# driver_V1_3.net
KiCad netlist of a schematic drawn in Altium Designer
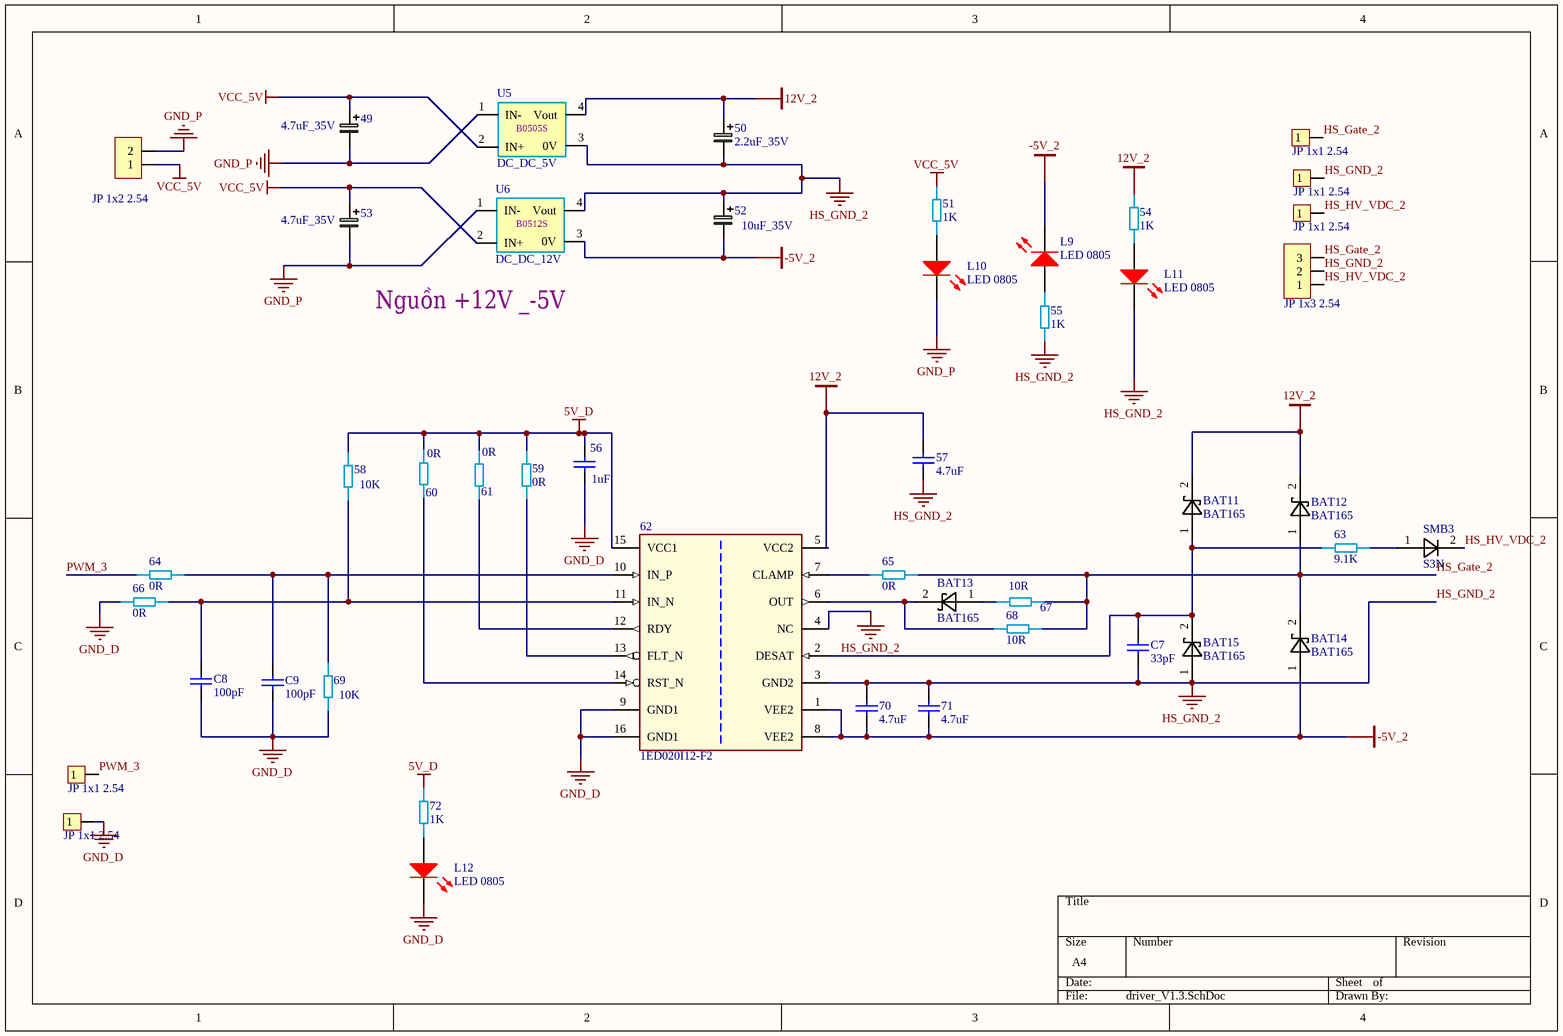
[diagram p0: driver_V1.3.SchDoc]

(export (version "E")
  (design (tool "Eeschema 10.0.6"))
  (components
    (comp (ref "49")
      (value "4.7uF_35V")
      (footprint "tu_4x5.4mm")
      (description "capacitor_electric")
      (libsource (lib "labari_altium1") (part "capacitor_electric"))
    )
    (comp (ref "50")
      (value "2.2uF_35V")
      (footprint "tu_4x5.4mm")
      (description "capacitor_electric")
      (libsource (lib "labari_altium1") (part "capacitor_electric"))
    )
    (comp (ref "51")
      (value "1K")
      (footprint "RES1206")
      (libsource (lib "labari_altium1") (part "311-0.0GRTR-ND"))
    )
    (comp (ref "52")
      (value "10uF_35V")
      (footprint "tu_4x5.4mm")
      (description "capacitor_electric")
      (libsource (lib "labari_altium1") (part "capacitor_electric"))
    )
    (comp (ref "53")
      (value "4.7uF_35V")
      (footprint "tu_4x5.4mm")
      (description "capacitor_electric")
      (libsource (lib "labari_altium1") (part "capacitor_electric"))
    )
    (comp (ref "54")
      (value "1K")
      (footprint "RES1206")
      (libsource (lib "labari_altium1") (part "311-0.0GRTR-ND"))
    )
    (comp (ref "55")
      (value "1K")
      (footprint "RES1206")
      (libsource (lib "labari_altium1") (part "311-0.0GRTR-ND"))
    )
    (comp (ref "56")
      (value "1uF")
      (footprint "Tu 0805_N")
      (libsource (lib "labari_altium1") (part "cap_0805"))
    )
    (comp (ref "57")
      (value "4.7uF")
      (footprint "tu 1206_N")
      (libsource (lib "labari_altium1") (part "cap_1210"))
    )
    (comp (ref "58")
      (value "10K")
      (footprint "RES1206")
      (libsource (lib "labari_altium1") (part "311-0.0GRTR-ND"))
    )
    (comp (ref "59")
      (value "0R")
      (footprint "RES1206")
      (libsource (lib "labari_altium1") (part "311-0.0GRTR-ND"))
    )
    (comp (ref "60")
      (value "0R")
      (footprint "RES1206")
      (libsource (lib "labari_altium1") (part "311-0.0GRTR-ND"))
    )
    (comp (ref "61")
      (value "0R")
      (footprint "RES1206")
      (libsource (lib "labari_altium1") (part "311-0.0GRTR-ND"))
    )
    (comp (ref "62")
      (value "1ED020I12-F2")
      (footprint "SOIC127P1028X264-16N-1")
      (description "Single IGBT Driver IC")
      (fields (field (name "MANUFACTURER") "Infineon Technologies"))
      (libsource (lib "labari_altium1") (part "1ED020I12-F2"))
    )
    (comp (ref "63")
      (value "9.1K")
      (footprint "RES_2512")
      (libsource (lib "labari_altium1") (part "311-0.0GRTR-ND"))
    )
    (comp (ref "64")
      (value "0R")
      (footprint "RES1206")
      (libsource (lib "labari_altium1") (part "311-0.0GRTR-ND"))
    )
    (comp (ref "65")
      (value "0R")
      (footprint "RES_2512")
      (libsource (lib "labari_altium1") (part "311-0.0GRTR-ND"))
    )
    (comp (ref "66")
      (value "0R")
      (footprint "RES1206")
      (libsource (lib "labari_altium1") (part "311-0.0GRTR-ND"))
    )
    (comp (ref "67")
      (value "10R")
      (footprint "RES_2512")
      (libsource (lib "labari_altium1") (part "311-0.0GRTR-ND"))
    )
    (comp (ref "68")
      (value "10R")
      (footprint "RES_2512")
      (libsource (lib "labari_altium1") (part "311-0.0GRTR-ND"))
    )
    (comp (ref "69")
      (value "10K")
      (footprint "RES1206")
      (libsource (lib "labari_altium1") (part "311-0.0GRTR-ND"))
    )
    (comp (ref "70")
      (value "4.7uF")
      (footprint "tu 1206_N")
      (libsource (lib "labari_altium1") (part "cap_1210"))
    )
    (comp (ref "71")
      (value "4.7uF")
      (footprint "tu 1206_N")
      (libsource (lib "labari_altium1") (part "cap_1210"))
    )
    (comp (ref "72")
      (value "1K")
      (footprint "RES1206")
      (libsource (lib "labari_altium1") (part "311-0.0GRTR-ND"))
    )
    (comp (ref "BAT11") (value "BAT165") (footprint "SMB") (libsource (lib "labari_altium1") (part "BAT165")))
    (comp (ref "BAT12") (value "BAT165") (footprint "SMB") (libsource (lib "labari_altium1") (part "BAT165")))
    (comp (ref "BAT13") (value "BAT165") (footprint "SMB") (libsource (lib "labari_altium1") (part "BAT165")))
    (comp (ref "BAT14") (value "BAT165") (footprint "SMB") (libsource (lib "labari_altium1") (part "BAT165")))
    (comp (ref "BAT15") (value "BAT165") (footprint "SMB") (libsource (lib "labari_altium1") (part "BAT165")))
    (comp (ref "C7")
      (value "33pF")
      (footprint "Tu 0805_N")
      (libsource (lib "labari_altium1") (part "cap_0805"))
    )
    (comp (ref "C8")
      (value "100pF")
      (footprint "Tu 0805_N")
      (libsource (lib "labari_altium1") (part "cap_0805"))
    )
    (comp (ref "C9")
      (value "100pF")
      (footprint "Tu 0805_N")
      (libsource (lib "labari_altium1") (part "cap_0805"))
    )
    (comp (ref "JP16")
      (value "JP 1x1 2.54")
      (footprint "test_point")
      (description "Cắm")
      (libsource (lib "labari_altium1") (part "JP 1x1 2.54 Duc Thang"))
    )
    (comp (ref "JP17")
      (value "JP 1x2 2.54")
      (footprint "JP 1x2 DT_n")
      (description "Cắm")
      (libsource (lib "labari_altium1") (part "JP 1x2 2.54 Duc Thang"))
    )
    (comp (ref "JP18")
      (value "JP 1x1 2.54")
      (footprint "test_point")
      (description "Cắm")
      (libsource (lib "labari_altium1") (part "JP 1x1 2.54 Duc Thang"))
    )
    (comp (ref "JP19")
      (value "JP 1x1 2.54")
      (footprint "test_point")
      (description "Cắm")
      (libsource (lib "labari_altium1") (part "JP 1x1 2.54 Duc Thang"))
    )
    (comp (ref "JP20")
      (value "JP 1x3 2.54")
      (footprint "XH2.54M-3")
      (description "Cắm")
      (libsource (lib "labari_altium1") (part "JP 1x3 2.54 Duc Cong"))
    )
    (comp (ref "JP21")
      (value "JP 1x1 2.54")
      (footprint "test_point")
      (description "Cắm")
      (libsource (lib "labari_altium1") (part "JP 1x1 2.54 Duc Thang"))
    )
    (comp (ref "JP22")
      (value "JP 1x1 2.54")
      (footprint "test_point")
      (description "Cắm")
      (libsource (lib "labari_altium1") (part "JP 1x1 2.54 Duc Thang"))
    )
    (comp (ref "L9")
      (value "LED 0805")
      (footprint "LED-0805-Red")
      (description "Dán")
      (libsource (lib "labari_altium1") (part "LED 0805 Do"))
    )
    (comp (ref "L10")
      (value "LED 0805")
      (footprint "LED-0805-Red")
      (description "Dán")
      (libsource (lib "labari_altium1") (part "LED 0805 Do"))
    )
    (comp (ref "L11")
      (value "LED 0805")
      (footprint "LED-0805-Red")
      (description "Dán")
      (libsource (lib "labari_altium1") (part "LED 0805 Do"))
    )
    (comp (ref "L12")
      (value "LED 0805")
      (footprint "LED-0805-Red")
      (description "Dán")
      (libsource (lib "labari_altium1") (part "LED 0805 Do"))
    )
    (comp (ref "SMB3") (value "S3N") (footprint "SMB") (libsource (lib "labari_altium1") (part "S3A-S3N")))
    (comp (ref "U5")
      (value "DC_DC_5V")
      (footprint "B0505S/D-1W")
      (libsource (lib "labari_altium1") (part "DC_DC_5v"))
    )
    (comp (ref "U6")
      (value "DC_DC_12V")
      (footprint "B0512S/D-1W")
      (libsource (lib "labari_altium1") (part "DC_DC_12v"))
    )
  )
  (nets
    (net (code "1") (name "-5V_2") (class "Default")
      (node (ref "52") (pin "2") (pinfunction "2_2") (pintype "passive"))
      (node (ref "62") (pin "1") (pinfunction "VEE2_1") (pintype "power_in"))
      (node (ref "62") (pin "8") (pinfunction "VEE2_8") (pintype "power_in"))
      (node (ref "70") (pin "1") (pinfunction "1_1") (pintype "passive"))
      (node (ref "71") (pin "1") (pinfunction "1_1") (pintype "passive"))
      (node (ref "BAT14") (pin "1") (pinfunction "1_1") (pintype "passive"))
      (node (ref "L9") (pin "2") (pinfunction "K_2") (pintype "passive"))
      (node (ref "U6") (pin "3") (pinfunction "0V_3") (pintype "passive"))
    )
    (net (code "2") (name "/HS_Gate_2") (class "Default")
      (node (ref "65") (pin "2") (pinfunction "2_2") (pintype "passive"))
      (node (ref "67") (pin "2") (pinfunction "2_2") (pintype "passive"))
      (node (ref "68") (pin "2") (pinfunction "2_2") (pintype "passive"))
      (node (ref "BAT12") (pin "1") (pinfunction "1_1") (pintype "passive"))
      (node (ref "BAT14") (pin "2") (pinfunction "2_2") (pintype "passive"))
      (node (ref "JP16") (pin "1") (pinfunction "1_1") (pintype "passive"))
      (node (ref "JP20") (pin "3") (pinfunction "3_3") (pintype "passive"))
    )
    (net (code "3") (name "/HS_HV_VDC_2") (class "Default")
      (node (ref "JP19") (pin "1") (pinfunction "1_1") (pintype "passive"))
      (node (ref "JP20") (pin "1") (pinfunction "1_1") (pintype "passive"))
      (node (ref "SMB3") (pin "2") (pinfunction "2_2") (pintype "passive"))
    )
    (net (code "4") (name "/PWM_3") (class "Default")
      (node (ref "64") (pin "2") (pinfunction "2_2") (pintype "passive"))
      (node (ref "JP21") (pin "1") (pinfunction "1_1") (pintype "passive"))
    )
    (net (code "5") (name "5V_D") (class "Default")
      (node (ref "56") (pin "2") (pinfunction "2_2") (pintype "passive"))
      (node (ref "58") (pin "2") (pinfunction "2_2") (pintype "passive"))
      (node (ref "59") (pin "1") (pinfunction "1_1") (pintype "passive"))
      (node (ref "60") (pin "2") (pinfunction "2_2") (pintype "passive"))
      (node (ref "61") (pin "1") (pinfunction "1_1") (pintype "passive"))
      (node (ref "62") (pin "15") (pinfunction "VCC1_15") (pintype "power_in"))
      (node (ref "72") (pin "1") (pinfunction "1_1") (pintype "passive"))
    )
    (net (code "6") (name "12V_2") (class "Default")
      (node (ref "50") (pin "1") (pinfunction "1_1") (pintype "passive"))
      (node (ref "54") (pin "1") (pinfunction "1_1") (pintype "passive"))
      (node (ref "57") (pin "2") (pinfunction "2_2") (pintype "passive"))
      (node (ref "62") (pin "5") (pinfunction "VCC2_5") (pintype "power_in"))
      (node (ref "BAT11") (pin "2") (pinfunction "2_2") (pintype "passive"))
      (node (ref "BAT12") (pin "2") (pinfunction "2_2") (pintype "passive"))
      (node (ref "U5") (pin "4") (pinfunction "Vout_4") (pintype "passive"))
    )
    (net (code "7") (name "GND_D") (class "Default")
      (node (ref "56") (pin "1") (pinfunction "1_1") (pintype "passive"))
      (node (ref "62") (pin "16") (pinfunction "GND1_16") (pintype "power_in"))
      (node (ref "62") (pin "9") (pinfunction "GND1_9") (pintype "power_in"))
      (node (ref "66") (pin "2") (pinfunction "2_2") (pintype "passive"))
      (node (ref "69") (pin "1") (pinfunction "1_1") (pintype "passive"))
      (node (ref "C8") (pin "1") (pinfunction "1_1") (pintype "passive"))
      (node (ref "C9") (pin "1") (pinfunction "1_1") (pintype "passive"))
      (node (ref "JP22") (pin "1") (pinfunction "1_1") (pintype "passive"))
      (node (ref "L12") (pin "2") (pinfunction "K_2") (pintype "passive"))
    )
    (net (code "8") (name "GND_P") (class "Default")
      (node (ref "49") (pin "2") (pinfunction "2_2") (pintype "passive"))
      (node (ref "53") (pin "2") (pinfunction "2_2") (pintype "passive"))
      (node (ref "JP17") (pin "2") (pinfunction "2_2") (pintype "passive"))
      (node (ref "L10") (pin "2") (pinfunction "K_2") (pintype "passive"))
      (node (ref "U5") (pin "1") (pinfunction "IN-_1") (pintype "passive"))
      (node (ref "U6") (pin "1") (pinfunction "IN-_1") (pintype "passive"))
    )
    (net (code "9") (name "HS_GND_2") (class "Default")
      (node (ref "50") (pin "2") (pinfunction "2_2") (pintype "passive"))
      (node (ref "52") (pin "1") (pinfunction "1_1") (pintype "passive"))
      (node (ref "55") (pin "2") (pinfunction "2_2") (pintype "passive"))
      (node (ref "57") (pin "1") (pinfunction "1_1") (pintype "passive"))
      (node (ref "62") (pin "3") (pinfunction "GND2_3") (pintype "power_in"))
      (node (ref "62") (pin "4") (pinfunction "NC_4") (pintype "passive"))
      (node (ref "70") (pin "2") (pinfunction "2_2") (pintype "passive"))
      (node (ref "71") (pin "2") (pinfunction "2_2") (pintype "passive"))
      (node (ref "BAT15") (pin "1") (pinfunction "1_1") (pintype "passive"))
      (node (ref "C7") (pin "1") (pinfunction "1_1") (pintype "passive"))
      (node (ref "JP18") (pin "1") (pinfunction "1_1") (pintype "passive"))
      (node (ref "JP20") (pin "2") (pinfunction "2_2") (pintype "passive"))
      (node (ref "L11") (pin "2") (pinfunction "K_2") (pintype "passive"))
      (node (ref "U5") (pin "3") (pinfunction "0V_3") (pintype "passive"))
      (node (ref "U6") (pin "4") (pinfunction "Vout_4") (pintype "passive"))
    )
    (net (code "10") (name "Net-(62-CLAMP)") (class "Default")
      (node (ref "62") (pin "7") (pinfunction "CLAMP_7") (pintype "input"))
      (node (ref "65") (pin "1") (pinfunction "1_1") (pintype "passive"))
    )
    (net (code "11") (name "Net-(62-DESAT)") (class "Default")
      (node (ref "62") (pin "2") (pinfunction "DESAT_2") (pintype "input"))
      (node (ref "63") (pin "1") (pinfunction "1_1") (pintype "passive"))
      (node (ref "BAT11") (pin "1") (pinfunction "1_1") (pintype "passive"))
      (node (ref "BAT15") (pin "2") (pinfunction "2_2") (pintype "passive"))
      (node (ref "C7") (pin "2") (pinfunction "2_2") (pintype "passive"))
    )
    (net (code "12") (name "Net-(62-FLT_N)") (class "Default")
      (node (ref "59") (pin "2") (pinfunction "2_2") (pintype "passive"))
      (node (ref "62") (pin "13") (pinfunction "FLT_N_13") (pintype "output"))
    )
    (net (code "13") (name "Net-(62-IN_N)") (class "Default")
      (node (ref "58") (pin "1") (pinfunction "1_1") (pintype "passive"))
      (node (ref "62") (pin "11") (pinfunction "IN_N_11") (pintype "input"))
      (node (ref "66") (pin "1") (pinfunction "1_1") (pintype "passive"))
      (node (ref "C8") (pin "2") (pinfunction "2_2") (pintype "passive"))
    )
    (net (code "14") (name "Net-(62-IN_P)") (class "Default")
      (node (ref "62") (pin "10") (pinfunction "IN_P_10") (pintype "input"))
      (node (ref "64") (pin "1") (pinfunction "1_1") (pintype "passive"))
      (node (ref "69") (pin "2") (pinfunction "2_2") (pintype "passive"))
      (node (ref "C9") (pin "2") (pinfunction "2_2") (pintype "passive"))
    )
    (net (code "15") (name "Net-(62-OUT)") (class "Default")
      (node (ref "62") (pin "6") (pinfunction "OUT_6") (pintype "output"))
      (node (ref "68") (pin "1") (pinfunction "1_1") (pintype "passive"))
      (node (ref "BAT13") (pin "2") (pinfunction "2_2") (pintype "passive"))
    )
    (net (code "16") (name "Net-(62-RDY)") (class "Default")
      (node (ref "61") (pin "2") (pinfunction "2_2") (pintype "passive"))
      (node (ref "62") (pin "12") (pinfunction "RDY_12") (pintype "output"))
    )
    (net (code "17") (name "Net-(62-RST_N)") (class "Default")
      (node (ref "60") (pin "1") (pinfunction "1_1") (pintype "passive"))
      (node (ref "62") (pin "14") (pinfunction "RST_N_14") (pintype "input"))
    )
    (net (code "18") (name "Net-(63-Pad2)") (class "Default")
      (node (ref "63") (pin "2") (pinfunction "2_2") (pintype "passive"))
      (node (ref "SMB3") (pin "1") (pinfunction "1_1") (pintype "passive"))
    )
    (net (code "19") (name "Net-(67-Pad1)") (class "Default")
      (node (ref "67") (pin "1") (pinfunction "1_1") (pintype "passive"))
      (node (ref "BAT13") (pin "1") (pinfunction "1_1") (pintype "passive"))
    )
    (net (code "20") (name "Net-(L9-A)") (class "Default")
      (node (ref "55") (pin "1") (pinfunction "1_1") (pintype "passive"))
      (node (ref "L9") (pin "1") (pinfunction "A_1") (pintype "passive"))
    )
    (net (code "21") (name "Net-(L10-A)") (class "Default")
      (node (ref "51") (pin "2") (pinfunction "2_2") (pintype "passive"))
      (node (ref "L10") (pin "1") (pinfunction "A_1") (pintype "passive"))
    )
    (net (code "22") (name "Net-(L11-A)") (class "Default")
      (node (ref "54") (pin "2") (pinfunction "2_2") (pintype "passive"))
      (node (ref "L11") (pin "1") (pinfunction "A_1") (pintype "passive"))
    )
    (net (code "23") (name "Net-(L12-A)") (class "Default")
      (node (ref "72") (pin "2") (pinfunction "2_2") (pintype "passive"))
      (node (ref "L12") (pin "1") (pinfunction "A_1") (pintype "passive"))
    )
    (net (code "24") (name "VCC_5V") (class "Default")
      (node (ref "49") (pin "1") (pinfunction "1_1") (pintype "passive"))
      (node (ref "51") (pin "1") (pinfunction "1_1") (pintype "passive"))
      (node (ref "53") (pin "1") (pinfunction "1_1") (pintype "passive"))
      (node (ref "JP17") (pin "1") (pinfunction "1_1") (pintype "passive"))
      (node (ref "U5") (pin "2") (pinfunction "IN+_2") (pintype "passive"))
      (node (ref "U6") (pin "2") (pinfunction "IN+_2") (pintype "passive"))
    )
  )
)
